# cell.net
KiCad netlist of a schematic drawn in EAGLE
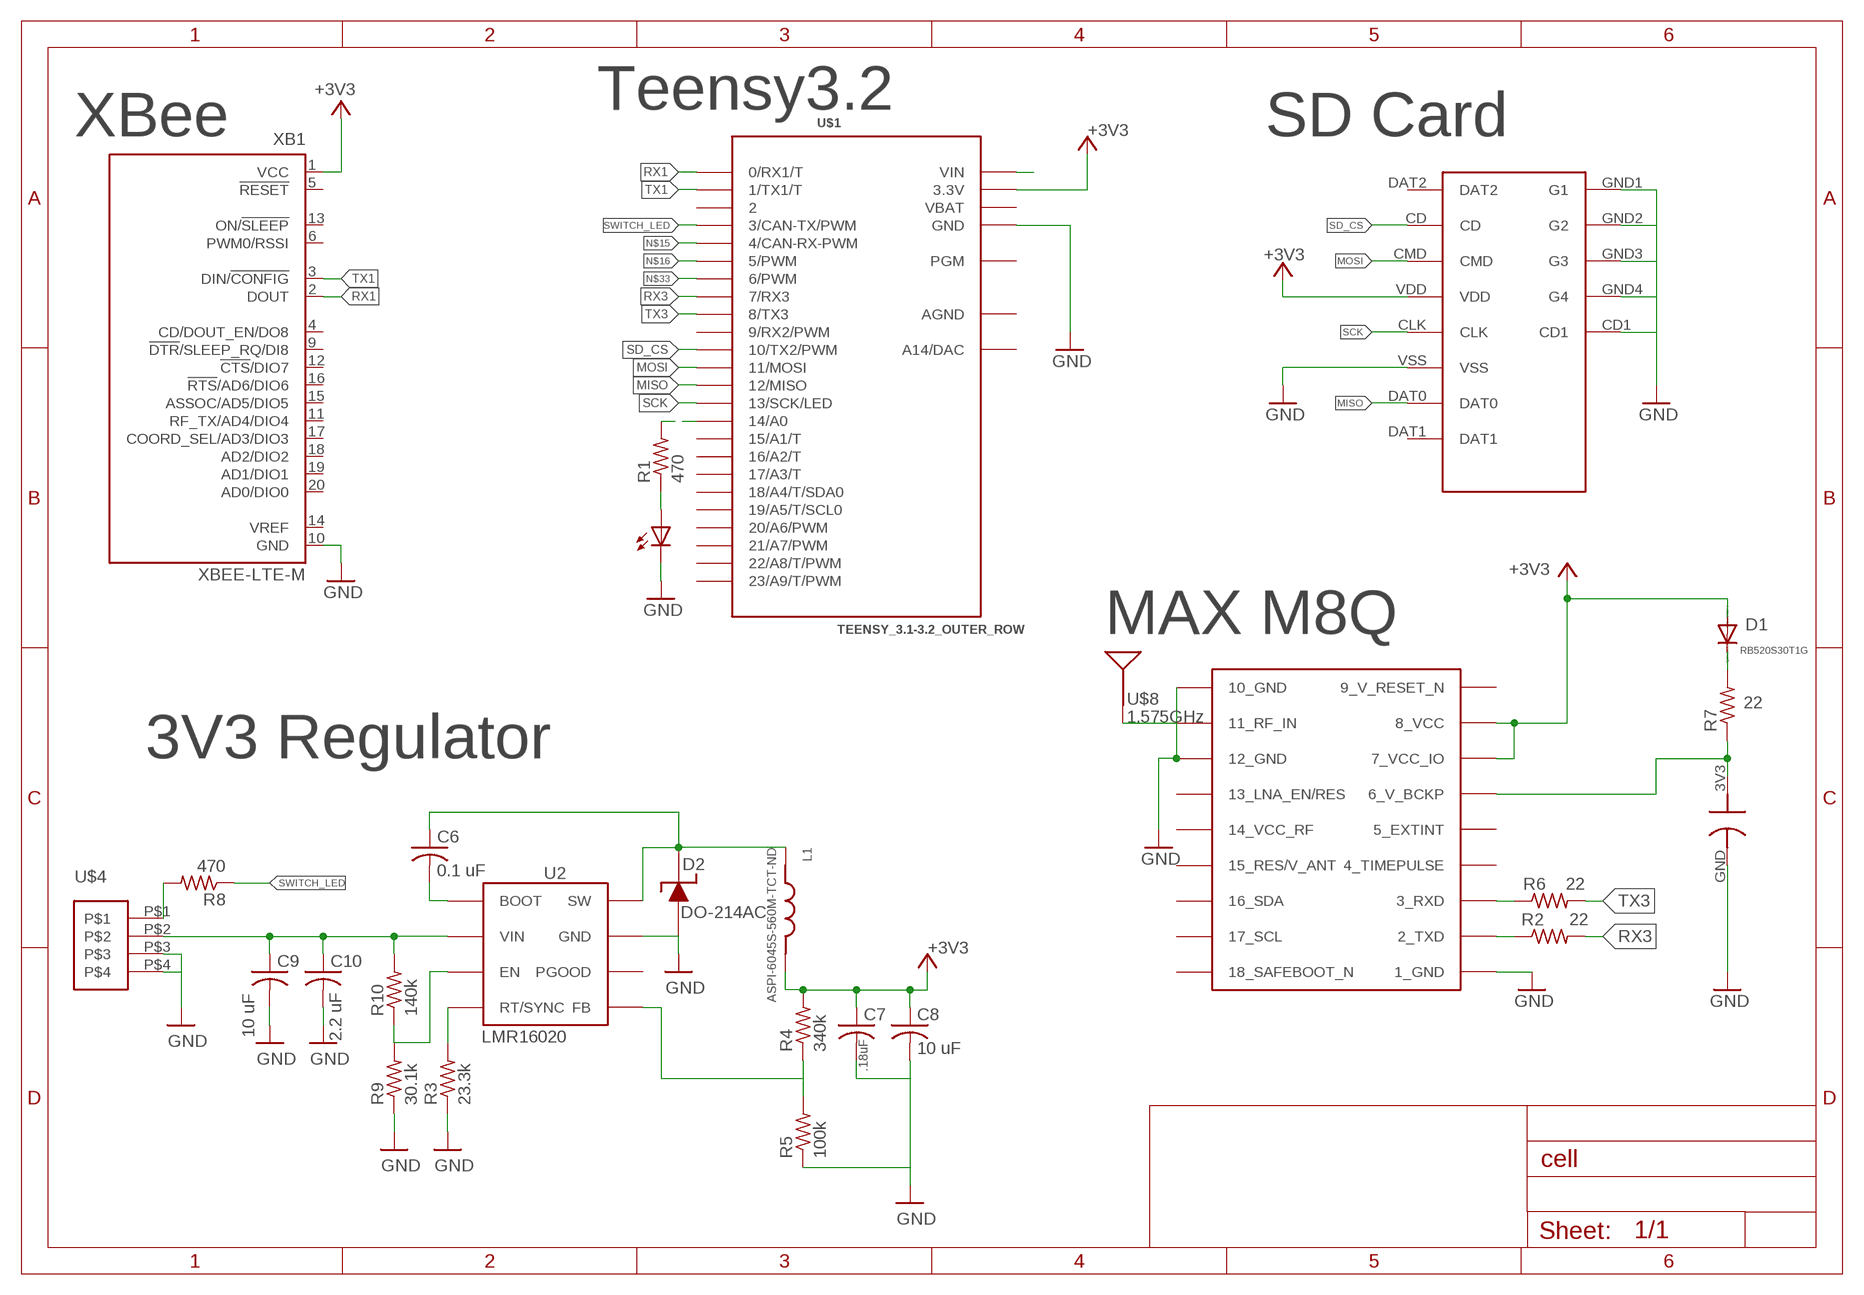
[diagram p0: schematic, sheet 1]

(export (version "E")
  (design (tool "Eeschema 10.0.6"))
  (components
    (comp (ref "C1")
      (value "DCK-3R3E204T614-E")
      (footprint "eagle-import:ELNASUPERCAP")
      (libsource (lib "eagle-import") (part "DCK-3R3E204T614-E"))
    )
    (comp (ref "C6")
      (value "0.1 uF")
      (footprint "eagle-import:C0805")
      (libsource (lib "eagle-import") (part "C-USC0805"))
    )
    (comp (ref "C7")
      (value ".18uF")
      (footprint "eagle-import:C0603")
      (libsource (lib "eagle-import") (part "C-USC0603"))
    )
    (comp (ref "C8")
      (value "10 uF")
      (footprint "eagle-import:C0603")
      (libsource (lib "eagle-import") (part "C-USC0603"))
    )
    (comp (ref "C9")
      (value "10 uF")
      (footprint "eagle-import:C1210")
      (libsource (lib "eagle-import") (part "C-USC1210"))
    )
    (comp (ref "C10")
      (value "2.2 uF")
      (footprint "eagle-import:C1210")
      (libsource (lib "eagle-import") (part "C-USC1210"))
    )
    (comp (ref "D1")
      (value "RB520S30T1G")
      (footprint "eagle-import:SOD523")
      (libsource (lib "eagle-import") (part "DIODE-SOD523"))
    )
    (comp (ref "D2")
      (value "DO-214AC")
      (footprint "eagle-import:DO-214AC")
      (libsource (lib "eagle-import") (part "DO-214AC"))
    )
    (comp (ref "L1")
      (value "ASPI-6045S-560M-TCT-ND")
      (footprint "eagle-import:ABRACON")
      (libsource (lib "eagle-import") (part "ASPI-6045S-560M-TCT-ND"))
    )
    (comp (ref "LED1")
      (value "Green")
      (footprint "eagle-import:CHIP-LED0603")
      (libsource (lib "eagle-import") (part "LEDCHIP-LED0603"))
    )
    (comp (ref "R1")
      (value "470")
      (footprint "eagle-import:R0603")
      (libsource (lib "eagle-import") (part "resistor_348_R-US_R0603"))
    )
    (comp (ref "R2")
      (value "22")
      (footprint "eagle-import:R0603")
      (libsource (lib "eagle-import") (part "R-US_R0603"))
    )
    (comp (ref "R3")
      (value "23.3k")
      (footprint "eagle-import:R0603")
      (libsource (lib "eagle-import") (part "resistor_R-US_R0603"))
    )
    (comp (ref "R4")
      (value "340k")
      (footprint "eagle-import:R0603")
      (libsource (lib "eagle-import") (part "resistor_R-US_R0603"))
    )
    (comp (ref "R5")
      (value "100k")
      (footprint "eagle-import:R0603")
      (libsource (lib "eagle-import") (part "resistor_R-US_R0603"))
    )
    (comp (ref "R6")
      (value "22")
      (footprint "eagle-import:R0603")
      (libsource (lib "eagle-import") (part "R-US_R0603"))
    )
    (comp (ref "R7")
      (value "22")
      (footprint "eagle-import:R0603")
      (libsource (lib "eagle-import") (part "resistor_348_R-US_R0603"))
    )
    (comp (ref "R8")
      (value "470")
      (footprint "eagle-import:R0603")
      (libsource (lib "eagle-import") (part "resistor_R-US_R0603"))
    )
    (comp (ref "R9")
      (value "30.1k")
      (footprint "eagle-import:R0603")
      (libsource (lib "eagle-import") (part "resistor_R-US_R0603"))
    )
    (comp (ref "R10")
      (value "140k")
      (footprint "eagle-import:R0603")
      (libsource (lib "eagle-import") (part "resistor_R-US_R0603"))
    )
    (comp (ref "U$1")
      (value "TEENSY_3.1-3.2_OUTER_ROW")
      (footprint "eagle-import:TEENSY_3.0-3.2&LC_OUTER_ROW")
      (libsource (lib "eagle-import") (part "TEENSY_3.1-3.2_OUTER_ROW"))
    )
    (comp (ref "U$3")
      (value "MICRO_SD")
      (footprint "eagle-import:MICRO_SD_HINGED")
      (libsource (lib "eagle-import") (part "MICRO_SD"))
    )
    (comp (ref "U$4")
      (value "MICROCLASP_4")
      (footprint "eagle-import:4_PIN_MICROCLASP")
      (libsource (lib "eagle-import") (part "MICROCLASP_4"))
    )
    (comp (ref "U$7")
      (value "MAX-M8")
      (footprint "eagle-import:MAX-M8")
      (libsource (lib "eagle-import") (part "MAX-M8"))
    )
    (comp (ref "U$8")
      (value "1.575GHz")
      (footprint "eagle-import:SPARKFUN-GPS_ANT-GPS-2X7MM")
      (libsource (lib "eagle-import") (part "SPARKFUN-GPS_ANTENNAGPS-2X7MM"))
    )
    (comp (ref "U2")
      (value "LMR16020")
      (footprint "eagle-import:SO8")
      (libsource (lib "eagle-import") (part "LMR16020"))
    )
    (comp (ref "XB1")
      (value "XBEE-LTE-M")
      (footprint "eagle-import:XBEE-PRO")
      (fields (field (name "MPN") "XBP24-AWI-001"))
      (libsource (lib "eagle-import") (part "XBEE-PRO"))
    )
  )
  (nets
    (net (code "1") (name "+3V3") (class "Default")
      (node (ref "C7") (pin "1") (pinfunction "1_1") (pintype "passive"))
      (node (ref "C8") (pin "1") (pinfunction "1_1") (pintype "passive"))
      (node (ref "D1") (pin "A") (pinfunction "A_A") (pintype "passive"))
      (node (ref "L1") (pin "P$2") (pinfunction "P$2_P$2") (pintype "bidirectional"))
      (node (ref "R4") (pin "2") (pinfunction "2_2") (pintype "passive"))
      (node (ref "U$1") (pin "3.3V") (pinfunction "3.3V_3.3V") (pintype "power_in"))
      (node (ref "U$1") (pin "3.3V1") (pinfunction "3.3V_3.3V1") (pintype "power_in"))
      (node (ref "U$3") (pin "VDD") (pinfunction "VDD_VDD") (pintype "bidirectional"))
      (node (ref "U$7") (pin "7_VCC_IO") (pinfunction "7_VCC_IO_7_VCC_IO") (pintype "power_in"))
      (node (ref "U$7") (pin "8_VCC") (pinfunction "8_VCC_8_VCC") (pintype "power_in"))
      (node (ref "XB1") (pin "1") (pinfunction "VCC_1") (pintype "power_in"))
    )
    (net (code "2") (name "/9_V_RESET_N") (class "Default")
      (node (ref "U$7") (pin "9_RESET_N") (pinfunction "9_V_RESET_N_9_RESET_N") (pintype "power_in"))
    )
    (net (code "3") (name "/AGND") (class "Default")
      (node (ref "U$1") (pin "AGND") (pinfunction "AGND_AGND") (pintype "power_in"))
    )
    (net (code "4") (name "/VBAT") (class "Default")
      (node (ref "U$1") (pin "VBAT") (pinfunction "VBAT_VBAT") (pintype "power_in"))
    )
    (net (code "5") (name "GND") (class "Default")
      (node (ref "C1") (pin "GND") (pinfunction "GND_GND") (pintype "bidirectional"))
      (node (ref "C10") (pin "2") (pinfunction "2_2") (pintype "passive"))
      (node (ref "C7") (pin "2") (pinfunction "2_2") (pintype "passive"))
      (node (ref "C8") (pin "2") (pinfunction "2_2") (pintype "passive"))
      (node (ref "C9") (pin "2") (pinfunction "2_2") (pintype "passive"))
      (node (ref "D2") (pin "P$1") (pinfunction "P$1_P$1") (pintype "bidirectional"))
      (node (ref "LED1") (pin "C") (pinfunction "C_C") (pintype "passive"))
      (node (ref "R3") (pin "1") (pinfunction "1_1") (pintype "passive"))
      (node (ref "R5") (pin "1") (pinfunction "1_1") (pintype "passive"))
      (node (ref "R9") (pin "1") (pinfunction "1_1") (pintype "passive"))
      (node (ref "U$1") (pin "GND") (pinfunction "GND_GND") (pintype "power_in"))
      (node (ref "U$1") (pin "GND1") (pinfunction "GND_GND1") (pintype "power_in"))
      (node (ref "U$3") (pin "CD1") (pinfunction "CD1_CD1") (pintype "bidirectional"))
      (node (ref "U$3") (pin "GND1") (pinfunction "G1_GND1") (pintype "bidirectional"))
      (node (ref "U$3") (pin "GND2") (pinfunction "G2_GND2") (pintype "bidirectional"))
      (node (ref "U$3") (pin "GND3") (pinfunction "G3_GND3") (pintype "bidirectional"))
      (node (ref "U$3") (pin "GND4") (pinfunction "G4_GND4") (pintype "bidirectional"))
      (node (ref "U$3") (pin "VSS") (pinfunction "VSS_VSS") (pintype "bidirectional"))
      (node (ref "U$4") (pin "P$3") (pinfunction "P$3_P$3") (pintype "bidirectional"))
      (node (ref "U$4") (pin "P$4") (pinfunction "P$4_P$4") (pintype "bidirectional"))
      (node (ref "U$7") (pin "10_GND") (pinfunction "10_GND_10_GND") (pintype "power_in"))
      (node (ref "U$7") (pin "12_GND") (pinfunction "12_GND_12_GND") (pintype "power_in"))
      (node (ref "U$7") (pin "1_GND") (pinfunction "1_GND_1_GND") (pintype "power_in"))
      (node (ref "U2") (pin "P$7") (pinfunction "GND_P$7") (pintype "bidirectional"))
      (node (ref "U2") (pin "PAD") (pinfunction "GND_PAD") (pintype "bidirectional"))
      (node (ref "XB1") (pin "10") (pinfunction "GND_10") (pintype "power_in"))
    )
    (net (code "6") (name "MISO") (class "Default")
      (node (ref "U$1") (pin "12") (pinfunction "12/MISO_12") (pintype "bidirectional"))
      (node (ref "U$3") (pin "DAT0") (pinfunction "DAT0_DAT0") (pintype "bidirectional"))
    )
    (net (code "7") (name "MOSI") (class "Default")
      (node (ref "U$1") (pin "11") (pinfunction "11/MOSI_11") (pintype "bidirectional"))
      (node (ref "U$3") (pin "CMD") (pinfunction "CMD_CMD") (pintype "bidirectional"))
    )
    (net (code "8") (name "N$15") (class "Default")
      (node (ref "U$1") (pin "4") (pinfunction "4/CAN-RX-PWM_4") (pintype "bidirectional"))
    )
    (net (code "9") (name "N$16") (class "Default")
      (node (ref "U$1") (pin "5") (pinfunction "5/PWM_5") (pintype "bidirectional"))
    )
    (net (code "10") (name "N$33") (class "Default")
      (node (ref "U$1") (pin "6") (pinfunction "6/PWM_6") (pintype "bidirectional"))
    )
    (net (code "11") (name "Net-(C1-Pad3V3)") (class "Default")
      (node (ref "C1") (pin "3V3") (pinfunction "3V3_3V3") (pintype "bidirectional"))
      (node (ref "R7") (pin "1") (pinfunction "1_1") (pintype "passive"))
      (node (ref "U$7") (pin "6_V_BCKP") (pinfunction "6_V_BCKP_6_V_BCKP") (pintype "bidirectional"))
    )
    (net (code "12") (name "Net-(D1-PadC)") (class "Default")
      (node (ref "D1") (pin "C") (pinfunction "C_C") (pintype "passive"))
      (node (ref "R7") (pin "2") (pinfunction "2_2") (pintype "passive"))
    )
    (net (code "13") (name "Net-(LED1-PadA)") (class "Default")
      (node (ref "LED1") (pin "A") (pinfunction "A_A") (pintype "passive"))
      (node (ref "R1") (pin "1") (pinfunction "1_1") (pintype "passive"))
    )
    (net (code "14") (name "Net-(R1-Pad2)") (class "Default")
      (node (ref "R1") (pin "2") (pinfunction "2_2") (pintype "passive"))
      (node (ref "U$1") (pin "14/A0") (pinfunction "14/A0_14/A0") (pintype "bidirectional"))
    )
    (net (code "15") (name "Net-(R2-Pad1)") (class "Default")
      (node (ref "R2") (pin "1") (pinfunction "1_1") (pintype "passive"))
      (node (ref "U$7") (pin "2_TXD") (pinfunction "2_TXD_2_TXD") (pintype "bidirectional"))
    )
    (net (code "16") (name "Net-(R6-Pad1)") (class "Default")
      (node (ref "R6") (pin "1") (pinfunction "1_1") (pintype "passive"))
      (node (ref "U$7") (pin "3_RXD") (pinfunction "3_RXD_3_RXD") (pintype "bidirectional"))
    )
    (net (code "17") (name "Net-(R8-Pad2)") (class "Default")
      (node (ref "R8") (pin "2") (pinfunction "2_2") (pintype "passive"))
      (node (ref "U$4") (pin "P$1") (pinfunction "P$1_P$1") (pintype "bidirectional"))
    )
    (net (code "18") (name "Net-(U$8-SIGNAL)") (class "Default")
      (node (ref "U$7") (pin "11_RF_IN") (pinfunction "11_RF_IN_11_RF_IN") (pintype "bidirectional"))
      (node (ref "U$8") (pin "1") (pinfunction "SIGNAL_1") (pintype "bidirectional"))
    )
    (net (code "19") (name "Net-(U2-BOOT)") (class "Default")
      (node (ref "C6") (pin "2") (pinfunction "2_2") (pintype "passive"))
      (node (ref "U2") (pin "P$1") (pinfunction "BOOT_P$1") (pintype "bidirectional"))
    )
    (net (code "20") (name "Net-(U2-EN)") (class "Default")
      (node (ref "R10") (pin "1") (pinfunction "1_1") (pintype "passive"))
      (node (ref "R9") (pin "2") (pinfunction "2_2") (pintype "passive"))
      (node (ref "U2") (pin "P$3") (pinfunction "EN_P$3") (pintype "bidirectional"))
    )
    (net (code "21") (name "Net-(U2-FB)") (class "Default")
      (node (ref "R4") (pin "1") (pinfunction "1_1") (pintype "passive"))
      (node (ref "R5") (pin "2") (pinfunction "2_2") (pintype "passive"))
      (node (ref "U2") (pin "P$5") (pinfunction "FB_P$5") (pintype "bidirectional"))
    )
    (net (code "22") (name "Net-(U2-RT{slash}SYNC)") (class "Default")
      (node (ref "R3") (pin "2") (pinfunction "2_2") (pintype "passive"))
      (node (ref "U2") (pin "P$4") (pinfunction "RT/SYNC_P$4") (pintype "bidirectional"))
    )
    (net (code "23") (name "Net-(U2-SW)") (class "Default")
      (node (ref "C6") (pin "1") (pinfunction "1_1") (pintype "passive"))
      (node (ref "D2") (pin "P$2") (pinfunction "P$2_P$2") (pintype "bidirectional"))
      (node (ref "L1") (pin "P$1") (pinfunction "P$1_P$1") (pintype "bidirectional"))
      (node (ref "U2") (pin "P$8") (pinfunction "SW_P$8") (pintype "bidirectional"))
    )
    (net (code "24") (name "Net-(U2-VIN)") (class "Default")
      (node (ref "C10") (pin "1") (pinfunction "1_1") (pintype "passive"))
      (node (ref "C9") (pin "1") (pinfunction "1_1") (pintype "passive"))
      (node (ref "R10") (pin "2") (pinfunction "2_2") (pintype "passive"))
      (node (ref "U$4") (pin "P$2") (pinfunction "P$2_P$2") (pintype "bidirectional"))
      (node (ref "U2") (pin "P$2") (pinfunction "VIN_P$2") (pintype "bidirectional"))
    )
    (net (code "25") (name "RX1") (class "Default")
      (node (ref "U$1") (pin "0") (pinfunction "0/RX1/T_0") (pintype "bidirectional"))
      (node (ref "XB1") (pin "2") (pinfunction "DOUT_2") (pintype "output"))
    )
    (net (code "26") (name "RX3") (class "Default")
      (node (ref "R2") (pin "2") (pinfunction "2_2") (pintype "passive"))
      (node (ref "U$1") (pin "7") (pinfunction "7/RX3_7") (pintype "bidirectional"))
    )
    (net (code "27") (name "SCK") (class "Default")
      (node (ref "U$1") (pin "13") (pinfunction "13/SCK/LED_13") (pintype "bidirectional"))
      (node (ref "U$3") (pin "CLK") (pinfunction "CLK_CLK") (pintype "bidirectional"))
    )
    (net (code "28") (name "SD_CS") (class "Default")
      (node (ref "U$1") (pin "10") (pinfunction "10/TX2/PWM_10") (pintype "bidirectional"))
      (node (ref "U$3") (pin "CD") (pinfunction "CD_CD") (pintype "bidirectional"))
    )
    (net (code "29") (name "SWITCH_LED") (class "Default")
      (node (ref "R8") (pin "1") (pinfunction "1_1") (pintype "passive"))
      (node (ref "U$1") (pin "3") (pinfunction "3/CAN-TX/PWM_3") (pintype "bidirectional"))
    )
    (net (code "30") (name "TX1") (class "Default")
      (node (ref "U$1") (pin "1") (pinfunction "1/TX1/T_1") (pintype "bidirectional"))
      (node (ref "XB1") (pin "3") (pinfunction "DIN/~{CONFIG}_3") (pintype "input"))
    )
    (net (code "31") (name "TX3") (class "Default")
      (node (ref "R6") (pin "2") (pinfunction "2_2") (pintype "passive"))
      (node (ref "U$1") (pin "8") (pinfunction "8/TX3_8") (pintype "bidirectional"))
    )
    (net (code "32") (name "unconnected-(U$1-9{slash}RX2{slash}PWM-Pad9)") (class "Default")
      (node (ref "U$1") (pin "9") (pinfunction "9/RX2/PWM_9") (pintype "bidirectional"))
    )
    (net (code "33") (name "unconnected-(U$1-15{slash}A1{slash}T-Pad15{slash}A1)") (class "Default")
      (node (ref "U$1") (pin "15/A1") (pinfunction "15/A1/T_15/A1") (pintype "bidirectional"))
    )
    (net (code "34") (name "unconnected-(U$1-16{slash}A2{slash}T-Pad16{slash}A2)") (class "Default")
      (node (ref "U$1") (pin "16/A2") (pinfunction "16/A2/T_16/A2") (pintype "bidirectional"))
    )
    (net (code "35") (name "unconnected-(U$1-17{slash}A3{slash}T-Pad17{slash}A3)") (class "Default")
      (node (ref "U$1") (pin "17/A3") (pinfunction "17/A3/T_17/A3") (pintype "bidirectional"))
    )
    (net (code "36") (name "unconnected-(U$1-18{slash}A4{slash}T{slash}SDA0-Pad18{slash}A4)") (class "Default")
      (node (ref "U$1") (pin "18/A4") (pinfunction "18/A4/T/SDA0_18/A4") (pintype "bidirectional"))
    )
    (net (code "37") (name "unconnected-(U$1-19{slash}A5{slash}T{slash}SCL0-Pad19{slash}A5)") (class "Default")
      (node (ref "U$1") (pin "19/A5") (pinfunction "19/A5/T/SCL0_19/A5") (pintype "bidirectional"))
    )
    (net (code "38") (name "unconnected-(U$1-20{slash}A6{slash}PWM-Pad20{slash}A6)") (class "Default")
      (node (ref "U$1") (pin "20/A6") (pinfunction "20/A6/PWM_20/A6") (pintype "bidirectional"))
    )
    (net (code "39") (name "unconnected-(U$1-21{slash}A7{slash}PWM-Pad21{slash}A7)") (class "Default")
      (node (ref "U$1") (pin "21/A7") (pinfunction "21/A7/PWM_21/A7") (pintype "bidirectional"))
    )
    (net (code "40") (name "unconnected-(U$1-22{slash}A8{slash}T{slash}PWM-Pad22{slash}A8)") (class "Default")
      (node (ref "U$1") (pin "22/A8") (pinfunction "22/A8/T/PWM_22/A8") (pintype "bidirectional"))
    )
    (net (code "41") (name "unconnected-(U$1-23{slash}A9{slash}T{slash}PWM-Pad23{slash}A9)") (class "Default")
      (node (ref "U$1") (pin "23/A9") (pinfunction "23/A9/T/PWM_23/A9") (pintype "bidirectional"))
    )
    (net (code "42") (name "unconnected-(U$1-A14{slash}DAC-PadRESET{slash}DAC)") (class "Default")
      (node (ref "U$1") (pin "RESET/DAC") (pinfunction "A14/DAC_RESET/DAC") (pintype "bidirectional"))
    )
    (net (code "43") (name "unconnected-(U$1-Pad2)") (class "Default")
      (node (ref "U$1") (pin "2") (pinfunction "2_2") (pintype "bidirectional"))
    )
    (net (code "44") (name "unconnected-(U$1-PadPGM)") (class "Default")
      (node (ref "U$1") (pin "PGM") (pinfunction "PGM_PGM") (pintype "bidirectional"))
    )
    (net (code "45") (name "unconnected-(U$1-PadVIN)") (class "Default")
      (node (ref "U$1") (pin "VIN") (pinfunction "VIN_VIN") (pintype "power_in"))
    )
    (net (code "46") (name "unconnected-(U$3-PadDAT1)") (class "Default")
      (node (ref "U$3") (pin "DAT1") (pinfunction "DAT1_DAT1") (pintype "bidirectional"))
    )
    (net (code "47") (name "unconnected-(U$3-PadDAT2)") (class "Default")
      (node (ref "U$3") (pin "DAT2") (pinfunction "DAT2_DAT2") (pintype "bidirectional"))
    )
    (net (code "48") (name "unconnected-(U$7-13_LNA_EN{slash}RES-Pad13_LNA_EN)") (class "Default")
      (node (ref "U$7") (pin "13_LNA_EN") (pinfunction "13_LNA_EN/RES_13_LNA_EN") (pintype "bidirectional"))
    )
    (net (code "49") (name "unconnected-(U$7-15_RES{slash}V_ANT-Pad15_V_ANT{slash}RESERVED)") (class "Default")
      (node (ref "U$7") (pin "15_V_ANT/RESERVED") (pinfunction "15_RES/V_ANT_15_V_ANT/RESERVED") (pintype "bidirectional"))
    )
    (net (code "50") (name "unconnected-(U$7-Pad4_TIMEPULSE)") (class "Default")
      (node (ref "U$7") (pin "4_TIMEPULSE") (pinfunction "4_TIMEPULSE_4_TIMEPULSE") (pintype "bidirectional"))
    )
    (net (code "51") (name "unconnected-(U$7-Pad5_EXTINT)") (class "Default")
      (node (ref "U$7") (pin "5_EXTINT") (pinfunction "5_EXTINT_5_EXTINT") (pintype "bidirectional"))
    )
    (net (code "52") (name "unconnected-(U$7-Pad14_VCC_RF)") (class "Default")
      (node (ref "U$7") (pin "14_VCC_RF") (pinfunction "14_VCC_RF_14_VCC_RF") (pintype "bidirectional"))
    )
    (net (code "53") (name "unconnected-(U$7-Pad16_SDA)") (class "Default")
      (node (ref "U$7") (pin "16_SDA") (pinfunction "16_SDA_16_SDA") (pintype "bidirectional"))
    )
    (net (code "54") (name "unconnected-(U$7-Pad17_SCL)") (class "Default")
      (node (ref "U$7") (pin "17_SCL") (pinfunction "17_SCL_17_SCL") (pintype "bidirectional"))
    )
    (net (code "55") (name "unconnected-(U$7-Pad18_SAFEBOOT_N)") (class "Default")
      (node (ref "U$7") (pin "18_SAFEBOOT_N") (pinfunction "18_SAFEBOOT_N_18_SAFEBOOT_N") (pintype "bidirectional"))
    )
    (net (code "56") (name "unconnected-(U2-PGOOD-PadP$6)") (class "Default")
      (node (ref "U2") (pin "P$6") (pinfunction "PGOOD_P$6") (pintype "bidirectional"))
    )
    (net (code "57") (name "unconnected-(XB1-AD0{slash}DIO0-Pad20)") (class "Default")
      (node (ref "XB1") (pin "20") (pinfunction "AD0/DIO0_20") (pintype "bidirectional"))
    )
    (net (code "58") (name "unconnected-(XB1-AD1{slash}DIO1-Pad19)") (class "Default")
      (node (ref "XB1") (pin "19") (pinfunction "AD1/DIO1_19") (pintype "bidirectional"))
    )
    (net (code "59") (name "unconnected-(XB1-AD2{slash}DIO2-Pad18)") (class "Default")
      (node (ref "XB1") (pin "18") (pinfunction "AD2/DIO2_18") (pintype "bidirectional"))
    )
    (net (code "60") (name "unconnected-(XB1-ASSOC{slash}AD5{slash}DIO5-Pad15)") (class "Default")
      (node (ref "XB1") (pin "15") (pinfunction "ASSOC/AD5/DIO5_15") (pintype "bidirectional"))
    )
    (net (code "61") (name "unconnected-(XB1-CD{slash}DOUT_EN{slash}DO8-Pad4)") (class "Default")
      (node (ref "XB1") (pin "4") (pinfunction "CD/DOUT_EN/DO8_4") (pintype "output"))
    )
    (net (code "62") (name "unconnected-(XB1-COORD_SEL{slash}AD3{slash}DIO3-Pad17)") (class "Default")
      (node (ref "XB1") (pin "17") (pinfunction "COORD_SEL/AD3/DIO3_17") (pintype "bidirectional"))
    )
    (net (code "63") (name "unconnected-(XB1-ON{slash}~{SLEEP}-Pad13)") (class "Default")
      (node (ref "XB1") (pin "13") (pinfunction "ON/~{SLEEP}_13") (pintype "output"))
    )
    (net (code "64") (name "unconnected-(XB1-PWM0{slash}RSSI-Pad6)") (class "Default")
      (node (ref "XB1") (pin "6") (pinfunction "PWM0/RSSI_6") (pintype "output"))
    )
    (net (code "65") (name "unconnected-(XB1-RF_TX{slash}AD4{slash}DIO4-Pad11)") (class "Default")
      (node (ref "XB1") (pin "11") (pinfunction "RF_TX/AD4/DIO4_11") (pintype "bidirectional"))
    )
    (net (code "66") (name "unconnected-(XB1-VREF-Pad14)") (class "Default")
      (node (ref "XB1") (pin "14") (pinfunction "VREF_14") (pintype "input"))
    )
    (net (code "67") (name "unconnected-(XB1-~{CTS}{slash}DIO7-Pad12)") (class "Default")
      (node (ref "XB1") (pin "12") (pinfunction "~{CTS}/DIO7_12") (pintype "bidirectional"))
    )
    (net (code "68") (name "unconnected-(XB1-~{DTR}{slash}SLEEP_RQ{slash}DI8-Pad9)") (class "Default")
      (node (ref "XB1") (pin "9") (pinfunction "~{DTR}/SLEEP_RQ/DI8_9") (pintype "bidirectional"))
    )
    (net (code "69") (name "unconnected-(XB1-~{RESET}-Pad5)") (class "Default")
      (node (ref "XB1") (pin "5") (pinfunction "~{RESET}_5") (pintype "input"))
    )
    (net (code "70") (name "unconnected-(XB1-~{RTS}{slash}AD6{slash}DIO6-Pad16)") (class "Default")
      (node (ref "XB1") (pin "16") (pinfunction "~{RTS}/AD6/DIO6_16") (pintype "bidirectional"))
    )
  )
)
